# Microcontroller.net
KiCad netlist of a schematic drawn in Altium Designer
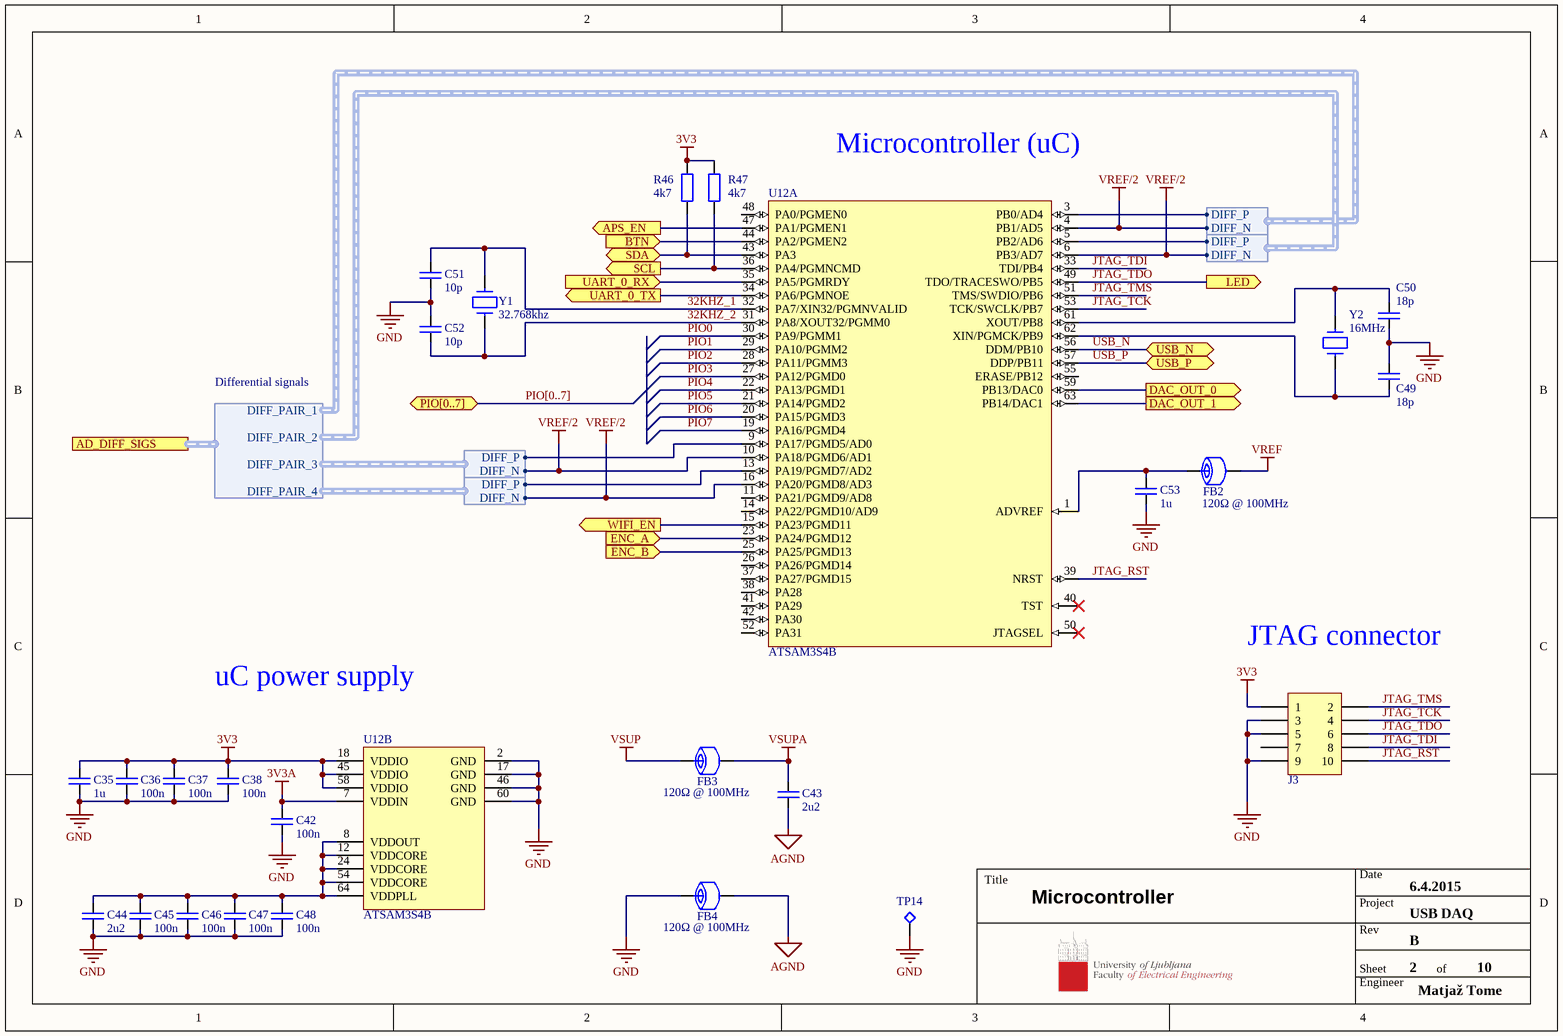
[diagram p0: Microcontroller.SchDoc]

(export (version "E")
  (design (tool "Eeschema 10.0.6"))
  (components
    (comp (ref "C35")
      (value "1u")
      (footprint "C_0603")
      (description "Generic capacitor")
      (fields (field (name "Comment") "comment"))
      (libsource (lib "DAQ") (part "Capacitor"))
    )
    (comp (ref "C36")
      (value "100n")
      (footprint "C_0603")
      (description "Generic capacitor")
      (fields (field (name "Comment") "comment"))
      (libsource (lib "DAQ") (part "Capacitor"))
    )
    (comp (ref "C37")
      (value "100n")
      (footprint "C_0603")
      (description "Generic capacitor")
      (fields (field (name "Comment") "comment"))
      (libsource (lib "DAQ") (part "Capacitor"))
    )
    (comp (ref "C38")
      (value "100n")
      (footprint "C_0603")
      (description "Generic capacitor")
      (fields (field (name "Comment") "comment"))
      (libsource (lib "DAQ") (part "Capacitor"))
    )
    (comp (ref "C42")
      (value "100n")
      (footprint "C_0603")
      (description "Generic capacitor")
      (fields (field (name "Comment") "comment"))
      (libsource (lib "DAQ") (part "Capacitor"))
    )
    (comp (ref "C43")
      (value "2u2")
      (footprint "C_0603")
      (description "Generic capacitor")
      (fields (field (name "Comment") "comment"))
      (libsource (lib "DAQ") (part "Capacitor"))
    )
    (comp (ref "C44")
      (value "2u2")
      (footprint "C_0603")
      (description "Generic capacitor")
      (fields (field (name "Comment") "comment"))
      (libsource (lib "DAQ") (part "Capacitor"))
    )
    (comp (ref "C45")
      (value "100n")
      (footprint "C_0603")
      (description "Generic capacitor")
      (fields (field (name "Comment") "comment"))
      (libsource (lib "DAQ") (part "Capacitor"))
    )
    (comp (ref "C46")
      (value "100n")
      (footprint "C_0603")
      (description "Generic capacitor")
      (fields (field (name "Comment") "comment"))
      (libsource (lib "DAQ") (part "Capacitor"))
    )
    (comp (ref "C47")
      (value "100n")
      (footprint "C_0603")
      (description "Generic capacitor")
      (fields (field (name "Comment") "comment"))
      (libsource (lib "DAQ") (part "Capacitor"))
    )
    (comp (ref "C48")
      (value "100n")
      (footprint "C_0603")
      (description "Generic capacitor")
      (fields (field (name "Comment") "comment"))
      (libsource (lib "DAQ") (part "Capacitor"))
    )
    (comp (ref "C49")
      (value "18p")
      (footprint "C_0603")
      (description "Generic capacitor")
      (fields (field (name "Comment") "comment"))
      (libsource (lib "DAQ") (part "Capacitor"))
    )
    (comp (ref "C50")
      (value "18p")
      (footprint "C_0603")
      (description "Generic capacitor")
      (fields (field (name "Comment") "comment"))
      (libsource (lib "DAQ") (part "Capacitor"))
    )
    (comp (ref "C51")
      (value "10p")
      (footprint "C_0603")
      (description "Generic capacitor")
      (fields (field (name "Comment") "comment"))
      (libsource (lib "DAQ") (part "Capacitor"))
    )
    (comp (ref "C52")
      (value "10p")
      (footprint "C_0603")
      (description "Generic capacitor")
      (fields (field (name "Comment") "comment"))
      (libsource (lib "DAQ") (part "Capacitor"))
    )
    (comp (ref "C53")
      (value "1u")
      (footprint "C_0603")
      (description "Generic capacitor")
      (fields (field (name "Comment") "comment"))
      (libsource (lib "DAQ") (part "Capacitor"))
    )
    (comp (ref "FB2")
      (value "120Ω @ 100MHz")
      (footprint "SMD_0805")
      (description "Ferrite Bead, 0805 [2012 Metric], 120 ohm, 800 mA, BLM21A Series, 0.15 ohm, ± 25%")
      (fields (field (name "MANUFACTURER") "Murata"))
      (libsource (lib "DAQ") (part "BLM21AG121SN1D"))
    )
    (comp (ref "FB3")
      (value "120Ω @ 100MHz")
      (footprint "SMD_0805")
      (description "Ferrite Bead, 0805 [2012 Metric], 120 ohm, 800 mA, BLM21A Series, 0.15 ohm, ± 25%")
      (fields (field (name "MANUFACTURER") "Murata"))
      (libsource (lib "DAQ") (part "BLM21AG121SN1D"))
    )
    (comp (ref "FB4")
      (value "120Ω @ 100MHz")
      (footprint "SMD_0805")
      (description "Ferrite Bead, 0805 [2012 Metric], 120 ohm, 800 mA, BLM21A Series, 0.15 ohm, ± 25%")
      (fields (field (name "MANUFACTURER") "Murata"))
      (libsource (lib "DAQ") (part "BLM21AG121SN1D"))
    )
    (comp (ref "J3")
      (value "M50-3600542")
      (footprint "HEADER_2X05_1.27mm")
      (description "Pin Header, Board-to-Board, 1.27 mm, 2 Rows, 10 Contacts, Surface Mount, Archer M50 Series")
      (fields (field (name "MANUFACTURER") "Harwin"))
      (libsource (lib "DAQ") (part "M50-3600542"))
    )
    (comp (ref "R46")
      (value "4k7")
      (footprint "R_0603")
      (description "Generic resistor")
      (fields (field (name "Comment") "comment"))
      (libsource (lib "DAQ") (part "Resistor"))
    )
    (comp (ref "R47")
      (value "4k7")
      (footprint "R_0603")
      (description "Generic resistor")
      (fields (field (name "Comment") "comment"))
      (libsource (lib "DAQ") (part "Resistor"))
    )
    (comp (ref "TP14")
      (value "testpoint")
      (footprint "TP1_FULL")
      (description "testpoint 1.5mm diameter no hole")
      (fields (field (name "PART NUMBER") "XXC0006"))
      (libsource (lib "DAQ") (part "Test Point"))
    )
    (comp (ref "U12")
      (value "ATSAM3S4B")
      (footprint "LQFP64")
      (description "Cortex M3 ARM microcontroller")
      (fields (field (name "PART NUMBER") "XAM0003") (field (name "MANUFACTURER") "Atmel"))
      (libsource (lib "DAQ") (part "ATSAM3SXB"))
    )
    (comp (ref "Y1")
      (value "32.768khz")
      (footprint "2X6_FLAT")
      (description "Crystal, 32.768 kHz, Cylinder Radial, 6.2mm x 2mm Dia, 12.5 pF, 20 ppm, R26 Series")
      (fields (field (name "PART NUMBER") "XCR0010") (field (name "MANUFACTURER") "RALTRON"))
      (libsource (lib "DAQ") (part "R26-32.768- 12.5"))
    )
    (comp (ref "Y2")
      (value "16MHz")
      (footprint "5X3.2")
      (description "Crystal, 16 MHz, SMD, 5mm x 3.2mm, 30 ppm, 18 pF, 30 ppm, 7A Series")
      (fields (field (name "MANUFACTURER") "TCX"))
      (libsource (lib "DAQ") (part "7A-16.000MAAJ-T"))
    )
  )
  (nets
    (net (code "5") (name "/32KHZ_1") (class "Default")
      (node (ref "C51") (pin "1") (pinfunction "1_1") (pintype "passive"))
      (node (ref "U12") (pin "32") (pinfunction "PA7/XIN32/PGMNVALID_32") (pintype "bidirectional"))
      (node (ref "Y1") (pin "2") (pinfunction "2_2") (pintype "passive"))
    )
    (net (code "6") (name "/32KHZ_2") (class "Default")
      (node (ref "C52") (pin "1") (pinfunction "1_1") (pintype "passive"))
      (node (ref "U12") (pin "31") (pinfunction "PA8/XOUT32/PGMM0_31") (pintype "bidirectional"))
      (node (ref "Y1") (pin "1") (pinfunction "1_1") (pintype "passive"))
    )
    (net (code "8") (name "/APS_EN") (class "Default")
      (node (ref "U12") (pin "47") (pinfunction "PA1/PGMEN1_47") (pintype "bidirectional"))
    )
    (net (code "9") (name "/BTN") (class "Default")
      (node (ref "U12") (pin "44") (pinfunction "PA2/PGMEN2_44") (pintype "bidirectional"))
    )
    (net (code "10") (name "/DAC_OUT_0") (class "Default")
      (node (ref "U12") (pin "59") (pinfunction "PB13/DAC0_59") (pintype "bidirectional"))
    )
    (net (code "11") (name "/DAC_OUT_1") (class "Default")
      (node (ref "U12") (pin "63") (pinfunction "PB14/DAC1_63") (pintype "bidirectional"))
    )
    (net (code "12") (name "/ENC_A") (class "Default")
      (node (ref "U12") (pin "23") (pinfunction "PA24/PGMD12_23") (pintype "bidirectional"))
    )
    (net (code "13") (name "/ENC_B") (class "Default")
      (node (ref "U12") (pin "25") (pinfunction "PA25/PGMD13_25") (pintype "bidirectional"))
    )
    (net (code "14") (name "/JTAG_RST") (class "Default")
      (node (ref "J3") (pin "10") (pinfunction "10_10") (pintype "passive"))
      (node (ref "U12") (pin "39") (pinfunction "NRST_39") (pintype "bidirectional"))
    )
    (net (code "15") (name "/JTAG_TCK") (class "Default")
      (node (ref "J3") (pin "4") (pinfunction "4_4") (pintype "passive"))
      (node (ref "U12") (pin "53") (pinfunction "TCK/SWCLK/PB7_53") (pintype "bidirectional"))
    )
    (net (code "16") (name "/JTAG_TDI") (class "Default")
      (node (ref "J3") (pin "8") (pinfunction "8_8") (pintype "passive"))
      (node (ref "U12") (pin "33") (pinfunction "TDI/PB4_33") (pintype "bidirectional"))
    )
    (net (code "17") (name "/JTAG_TDO") (class "Default")
      (node (ref "J3") (pin "6") (pinfunction "6_6") (pintype "passive"))
      (node (ref "U12") (pin "49") (pinfunction "TDO/TRACESWO/PB5_49") (pintype "bidirectional"))
    )
    (net (code "18") (name "/JTAG_TMS") (class "Default")
      (node (ref "J3") (pin "2") (pinfunction "2_2") (pintype "passive"))
      (node (ref "U12") (pin "51") (pinfunction "TMS/SWDIO/PB6_51") (pintype "bidirectional"))
    )
    (net (code "19") (name "/PIO0") (class "Default")
      (node (ref "U12") (pin "30") (pinfunction "PA9/PGMM1_30") (pintype "bidirectional"))
    )
    (net (code "20") (name "/PIO1") (class "Default")
      (node (ref "U12") (pin "29") (pinfunction "PA10/PGMM2_29") (pintype "bidirectional"))
    )
    (net (code "21") (name "/PIO2") (class "Default")
      (node (ref "U12") (pin "28") (pinfunction "PA11/PGMM3_28") (pintype "bidirectional"))
    )
    (net (code "22") (name "/PIO3") (class "Default")
      (node (ref "U12") (pin "27") (pinfunction "PA12/PGMD0_27") (pintype "bidirectional"))
    )
    (net (code "23") (name "/PIO4") (class "Default")
      (node (ref "U12") (pin "22") (pinfunction "PA13/PGMD1_22") (pintype "bidirectional"))
    )
    (net (code "24") (name "/PIO5") (class "Default")
      (node (ref "U12") (pin "21") (pinfunction "PA14/PGMD2_21") (pintype "bidirectional"))
    )
    (net (code "25") (name "/PIO6") (class "Default")
      (node (ref "U12") (pin "20") (pinfunction "PA15/PGMD3_20") (pintype "bidirectional"))
    )
    (net (code "26") (name "/PIO7") (class "Default")
      (node (ref "U12") (pin "19") (pinfunction "PA16/PGMD4_19") (pintype "bidirectional"))
    )
    (net (code "28") (name "/SCL") (class "Default")
      (node (ref "R47") (pin "1") (pintype "passive"))
      (node (ref "U12") (pin "36") (pinfunction "PA4/PGMNCMD_36") (pintype "bidirectional"))
    )
    (net (code "29") (name "/SDA") (class "Default")
      (node (ref "R46") (pin "1") (pintype "passive"))
      (node (ref "U12") (pin "43") (pinfunction "PA3_43") (pintype "bidirectional"))
    )
    (net (code "30") (name "/UART_0_RX") (class "Default")
      (node (ref "U12") (pin "35") (pinfunction "PA5/PGMRDY_35") (pintype "bidirectional"))
    )
    (net (code "31") (name "/UART_0_TX") (class "Default")
      (node (ref "U12") (pin "34") (pinfunction "PA6/PGMNOE_34") (pintype "bidirectional"))
    )
    (net (code "32") (name "/USB_N") (class "Default")
      (node (ref "U12") (pin "56") (pinfunction "DDM/PB10_56") (pintype "bidirectional"))
    )
    (net (code "33") (name "/USB_P") (class "Default")
      (node (ref "U12") (pin "57") (pinfunction "DDP/PB11_57") (pintype "bidirectional"))
    )
    (net (code "34") (name "/WIFI_EN") (class "Default")
      (node (ref "U12") (pin "15") (pinfunction "PA23/PGMD11_15") (pintype "bidirectional"))
    )
    (net (code "36") (name "3V3") (class "Default")
      (node (ref "C35") (pin "1") (pinfunction "1_1") (pintype "passive"))
      (node (ref "C36") (pin "1") (pinfunction "1_1") (pintype "passive"))
      (node (ref "C37") (pin "1") (pinfunction "1_1") (pintype "passive"))
      (node (ref "C38") (pin "1") (pinfunction "1_1") (pintype "passive"))
      (node (ref "J3") (pin "1") (pinfunction "1_1") (pintype "passive"))
      (node (ref "R46") (pin "2") (pintype "passive"))
      (node (ref "R47") (pin "2") (pintype "passive"))
      (node (ref "U12") (pin "18") (pinfunction "VDDIO_18") (pintype "power_in"))
      (node (ref "U12") (pin "45") (pinfunction "VDDIO_45") (pintype "power_in"))
      (node (ref "U12") (pin "58") (pinfunction "VDDIO_58") (pintype "power_in"))
    )
    (net (code "37") (name "3V3A") (class "Default")
      (node (ref "C42") (pin "1") (pinfunction "1_1") (pintype "passive"))
      (node (ref "U12") (pin "7") (pinfunction "VDDIN_7") (pintype "power_in"))
    )
    (net (code "38") (name "AGND") (class "Default")
      (node (ref "C43") (pin "2") (pinfunction "2_2") (pintype "passive"))
      (node (ref "FB4") (pin "2") (pintype "passive"))
    )
    (net (code "39") (name "GND") (class "Default")
      (node (ref "C35") (pin "2") (pinfunction "2_2") (pintype "passive"))
      (node (ref "C36") (pin "2") (pinfunction "2_2") (pintype "passive"))
      (node (ref "C37") (pin "2") (pinfunction "2_2") (pintype "passive"))
      (node (ref "C38") (pin "2") (pinfunction "2_2") (pintype "passive"))
      (node (ref "C42") (pin "2") (pinfunction "2_2") (pintype "passive"))
      (node (ref "C44") (pin "2") (pinfunction "2_2") (pintype "passive"))
      (node (ref "C45") (pin "2") (pinfunction "2_2") (pintype "passive"))
      (node (ref "C46") (pin "2") (pinfunction "2_2") (pintype "passive"))
      (node (ref "C47") (pin "2") (pinfunction "2_2") (pintype "passive"))
      (node (ref "C48") (pin "2") (pinfunction "2_2") (pintype "passive"))
      (node (ref "C49") (pin "2") (pinfunction "2_2") (pintype "passive"))
      (node (ref "C50") (pin "2") (pinfunction "2_2") (pintype "passive"))
      (node (ref "C51") (pin "2") (pinfunction "2_2") (pintype "passive"))
      (node (ref "C52") (pin "2") (pinfunction "2_2") (pintype "passive"))
      (node (ref "C53") (pin "2") (pinfunction "2_2") (pintype "passive"))
      (node (ref "FB4") (pin "1") (pintype "passive"))
      (node (ref "J3") (pin "3") (pinfunction "3_3") (pintype "passive"))
      (node (ref "J3") (pin "5") (pinfunction "5_5") (pintype "passive"))
      (node (ref "J3") (pin "9") (pinfunction "9_9") (pintype "passive"))
      (node (ref "TP14") (pin "1") (pinfunction "1_1") (pintype "passive"))
      (node (ref "U12") (pin "17") (pinfunction "GND_17") (pintype "power_in"))
      (node (ref "U12") (pin "2") (pinfunction "GND_2") (pintype "power_in"))
      (node (ref "U12") (pin "46") (pinfunction "GND_46") (pintype "power_in"))
      (node (ref "U12") (pin "60") (pinfunction "GND_60") (pintype "power_in"))
    )
    (net (code "40") (name "Net-(U12A-ADVREF)") (class "Default")
      (node (ref "C53") (pin "1") (pinfunction "1_1") (pintype "passive"))
      (node (ref "FB2") (pin "1") (pintype "passive"))
      (node (ref "U12") (pin "1") (pinfunction "ADVREF_1") (pintype "input"))
    )
    (net (code "41") (name "Net-(U12A-XIN{slash}PGMCK{slash}PB9)") (class "Default")
      (node (ref "C49") (pin "1") (pinfunction "1_1") (pintype "passive"))
      (node (ref "U12") (pin "62") (pinfunction "XIN/PGMCK/PB9_62") (pintype "bidirectional"))
      (node (ref "Y2") (pin "1") (pinfunction "1_1") (pintype "passive"))
    )
    (net (code "42") (name "Net-(U12A-XOUT{slash}PB8)") (class "Default")
      (node (ref "C50") (pin "1") (pinfunction "1_1") (pintype "passive"))
      (node (ref "U12") (pin "61") (pinfunction "XOUT/PB8_61") (pintype "bidirectional"))
      (node (ref "Y2") (pin "2") (pinfunction "2_2") (pintype "passive"))
    )
    (net (code "43") (name "Net-(U12B-VDDOUT)") (class "Default")
      (node (ref "C44") (pin "1") (pinfunction "1_1") (pintype "passive"))
      (node (ref "C45") (pin "1") (pinfunction "1_1") (pintype "passive"))
      (node (ref "C46") (pin "1") (pinfunction "1_1") (pintype "passive"))
      (node (ref "C47") (pin "1") (pinfunction "1_1") (pintype "passive"))
      (node (ref "C48") (pin "1") (pinfunction "1_1") (pintype "passive"))
      (node (ref "U12") (pin "12") (pinfunction "VDDCORE_12") (pintype "power_in"))
      (node (ref "U12") (pin "24") (pinfunction "VDDCORE_24") (pintype "power_in"))
      (node (ref "U12") (pin "54") (pinfunction "VDDCORE_54") (pintype "power_in"))
      (node (ref "U12") (pin "64") (pinfunction "VDDPLL_64") (pintype "power_in"))
      (node (ref "U12") (pin "8") (pinfunction "VDDOUT_8") (pintype "power_in"))
    )
    (net (code "44") (name "VREF") (class "Default") (node (ref "FB2") (pin "2") (pintype "passive")))
    (net (code "45") (name "VREF{slash}2") (class "Default")
      (node (ref "U12") (pin "10") (pinfunction "PA18/PGMD6/AD1_10") (pintype "bidirectional"))
      (node (ref "U12") (pin "16") (pinfunction "PA20/PGMD8/AD3_16") (pintype "bidirectional"))
      (node (ref "U12") (pin "4") (pinfunction "PB1/AD5_4") (pintype "bidirectional"))
      (node (ref "U12") (pin "6") (pinfunction "PB3/AD7_6") (pintype "bidirectional"))
    )
    (net (code "46") (name "VSUP") (class "Default") (node (ref "FB3") (pin "1") (pintype "passive")))
    (net (code "47") (name "VSUPA") (class "Default")
      (node (ref "C43") (pin "1") (pinfunction "1_1") (pintype "passive"))
      (node (ref "FB3") (pin "2") (pintype "passive"))
    )
    (net (code "48") (name "unconnected-(J3-Pad7)") (class "Default")
      (node (ref "J3") (pin "7") (pinfunction "7_7") (pintype "passive"))
    )
    (net (code "49") (name "unconnected-(U12A-ERASE{slash}PB12-Pad55)") (class "Default")
      (node (ref "U12") (pin "55") (pinfunction "ERASE/PB12_55") (pintype "bidirectional"))
    )
    (net (code "50") (name "unconnected-(U12A-JTAGSEL-Pad50)") (class "Default")
      (node (ref "U12") (pin "50") (pinfunction "JTAGSEL_50") (pintype "input+no_connect"))
    )
    (net (code "51") (name "unconnected-(U12A-PA0{slash}PGMEN0-Pad48)") (class "Default")
      (node (ref "U12") (pin "48") (pinfunction "PA0/PGMEN0_48") (pintype "bidirectional"))
    )
    (net (code "52") (name "unconnected-(U12A-PA17{slash}PGMD5{slash}AD0-Pad9)") (class "Default")
      (node (ref "U12") (pin "9") (pinfunction "PA17/PGMD5/AD0_9") (pintype "bidirectional"))
    )
    (net (code "53") (name "unconnected-(U12A-PA19{slash}PGMD7{slash}AD2-Pad13)") (class "Default")
      (node (ref "U12") (pin "13") (pinfunction "PA19/PGMD7/AD2_13") (pintype "bidirectional"))
    )
    (net (code "54") (name "unconnected-(U12A-PA21{slash}PGMD9{slash}AD8-Pad11)") (class "Default")
      (node (ref "U12") (pin "11") (pinfunction "PA21/PGMD9/AD8_11") (pintype "bidirectional"))
    )
    (net (code "55") (name "unconnected-(U12A-PA22{slash}PGMD10{slash}AD9-Pad14)") (class "Default")
      (node (ref "U12") (pin "14") (pinfunction "PA22/PGMD10/AD9_14") (pintype "bidirectional"))
    )
    (net (code "56") (name "unconnected-(U12A-PA26{slash}PGMD14-Pad26)") (class "Default")
      (node (ref "U12") (pin "26") (pinfunction "PA26/PGMD14_26") (pintype "bidirectional"))
    )
    (net (code "57") (name "unconnected-(U12A-PA27{slash}PGMD15-Pad37)") (class "Default")
      (node (ref "U12") (pin "37") (pinfunction "PA27/PGMD15_37") (pintype "bidirectional"))
    )
    (net (code "58") (name "unconnected-(U12A-PA28-Pad38)") (class "Default")
      (node (ref "U12") (pin "38") (pinfunction "PA28_38") (pintype "bidirectional"))
    )
    (net (code "59") (name "unconnected-(U12A-PA29-Pad41)") (class "Default")
      (node (ref "U12") (pin "41") (pinfunction "PA29_41") (pintype "bidirectional"))
    )
    (net (code "60") (name "unconnected-(U12A-PA30-Pad42)") (class "Default")
      (node (ref "U12") (pin "42") (pinfunction "PA30_42") (pintype "bidirectional"))
    )
    (net (code "61") (name "unconnected-(U12A-PA31-Pad52)") (class "Default")
      (node (ref "U12") (pin "52") (pinfunction "PA31_52") (pintype "bidirectional"))
    )
    (net (code "62") (name "unconnected-(U12A-PB0{slash}AD4-Pad3)") (class "Default")
      (node (ref "U12") (pin "3") (pinfunction "PB0/AD4_3") (pintype "bidirectional"))
    )
    (net (code "63") (name "unconnected-(U12A-PB2{slash}AD6-Pad5)") (class "Default")
      (node (ref "U12") (pin "5") (pinfunction "PB2/AD6_5") (pintype "bidirectional"))
    )
    (net (code "64") (name "unconnected-(U12A-TST-Pad40)") (class "Default")
      (node (ref "U12") (pin "40") (pinfunction "TST_40") (pintype "input+no_connect"))
    )
  )
)
